# USBBreakout-1_3.net
KiCad netlist of a schematic drawn in EAGLE
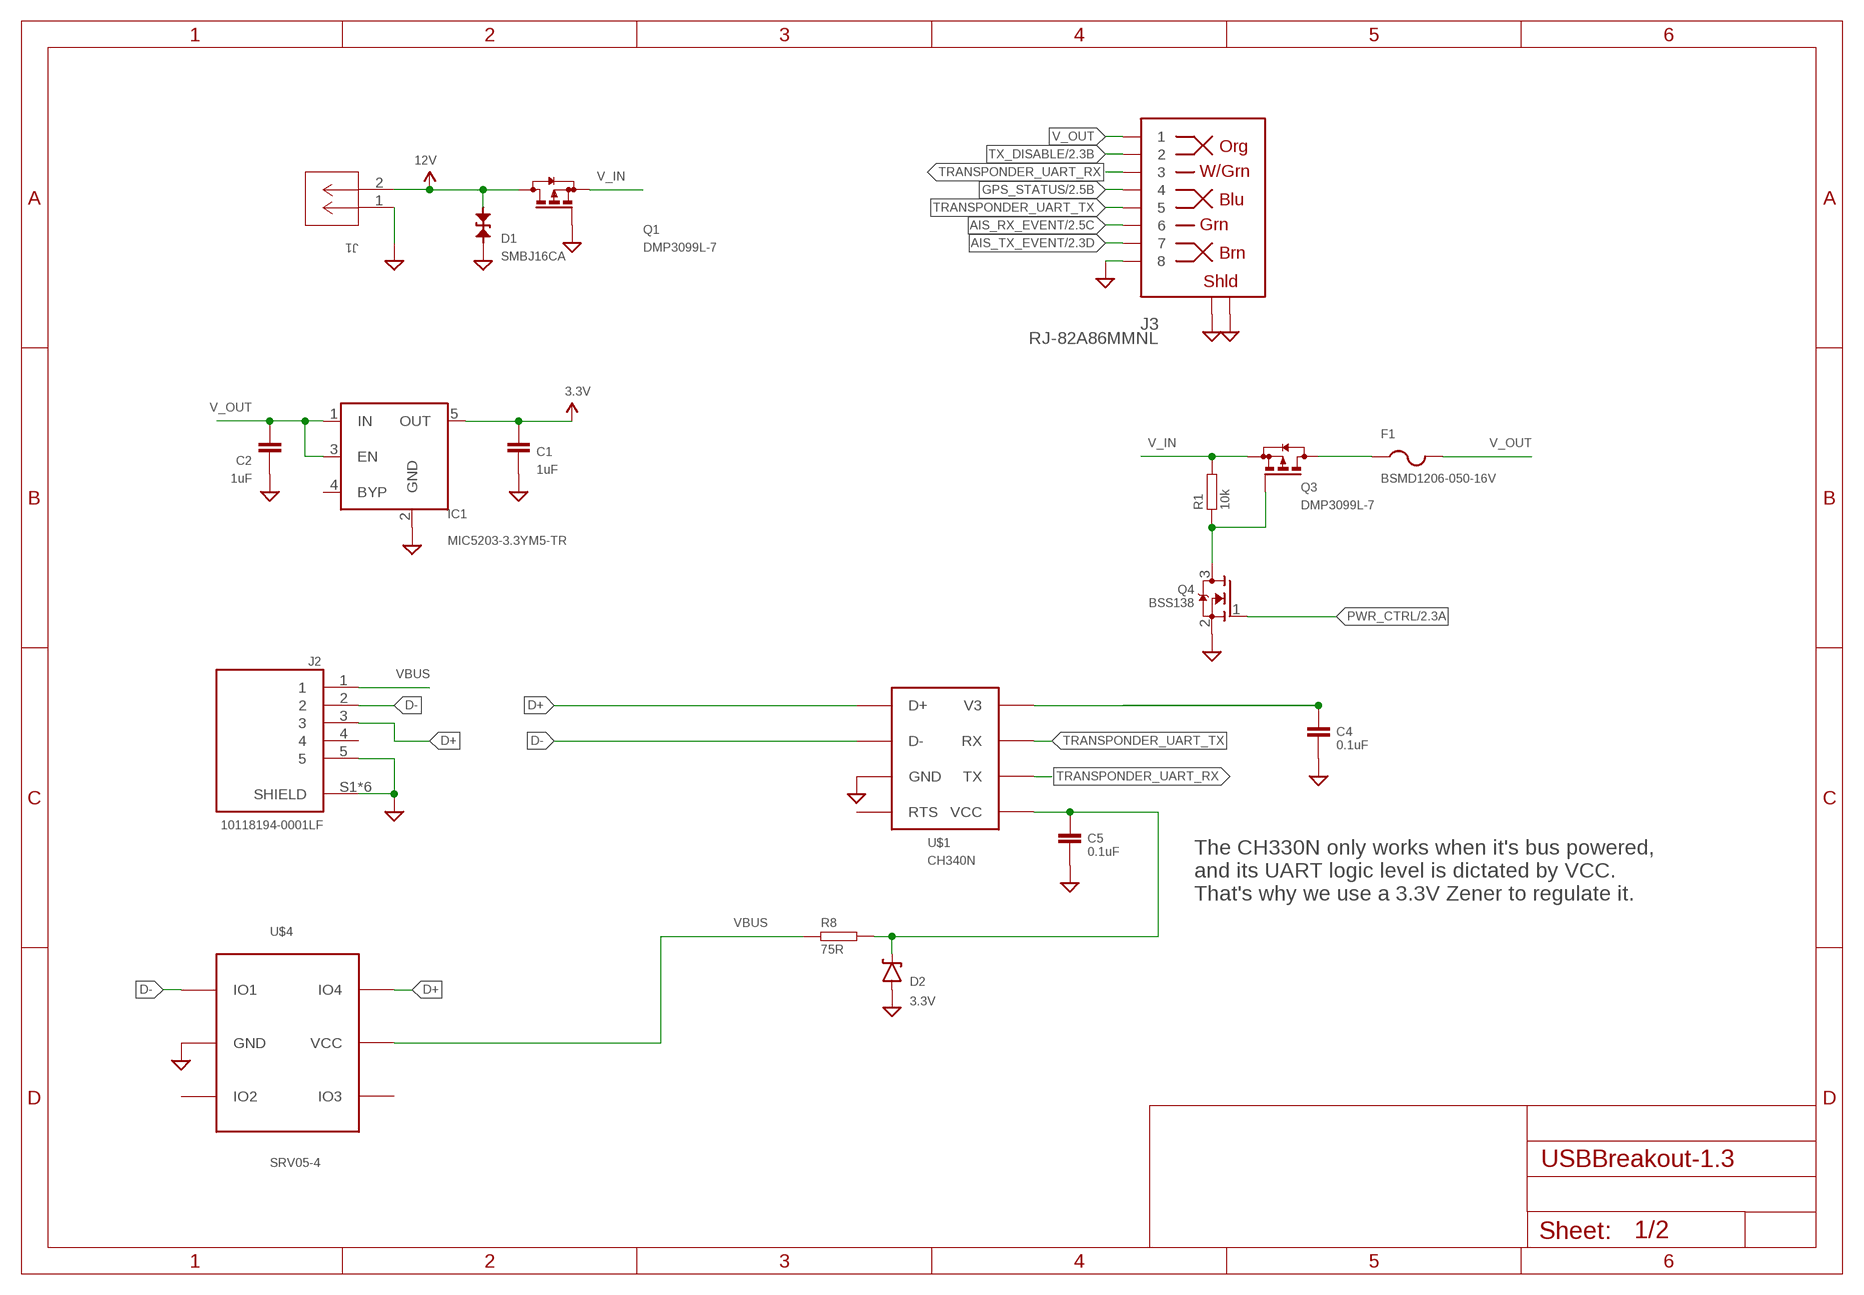
[diagram p0: schematic, sheet 1]
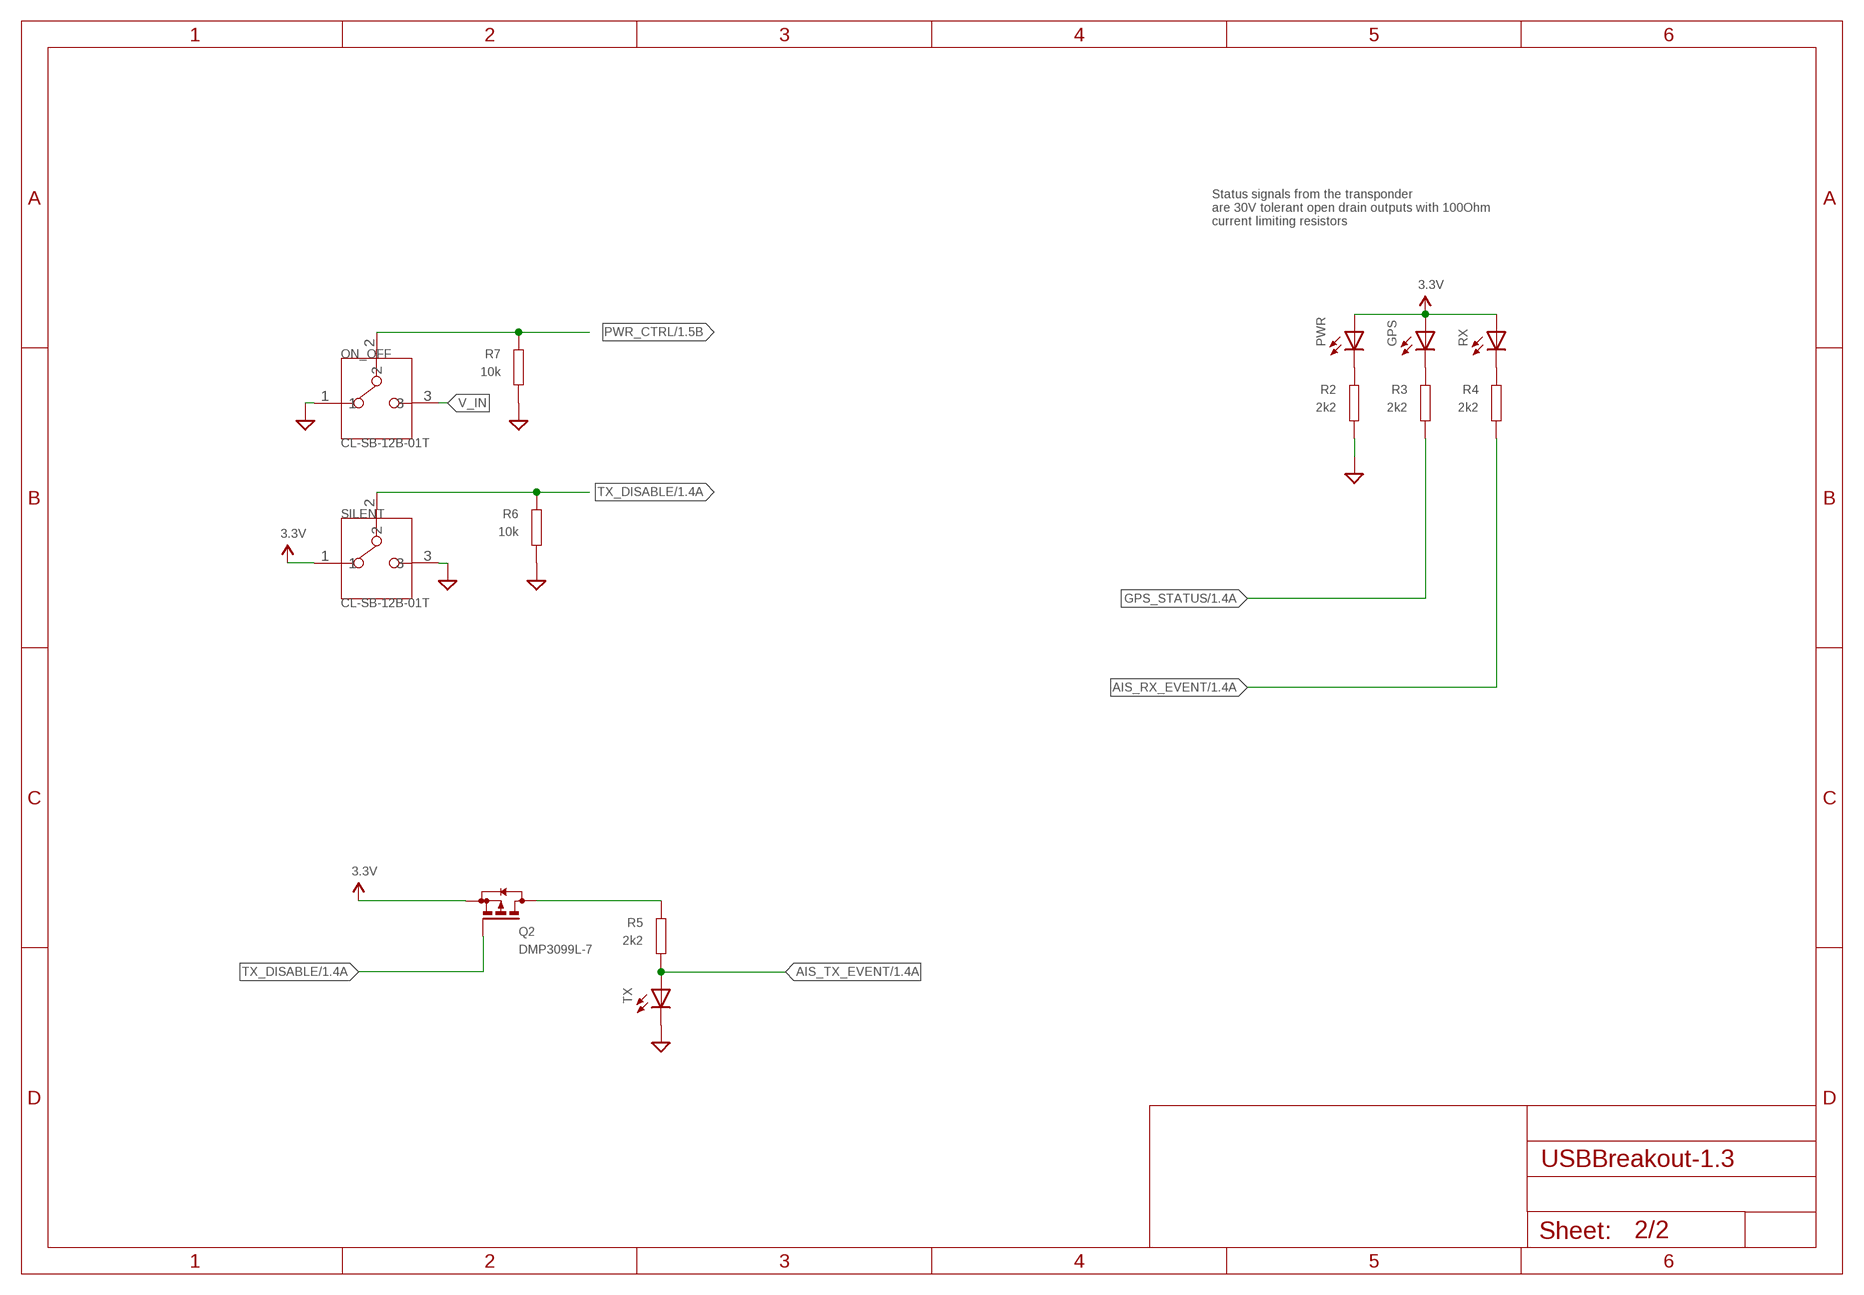
[diagram p1: schematic, sheet 2]

(export (version "E")
  (design (tool "Eeschema 10.0.6"))
  (components
    (comp (ref "GPS")
      (value "LEDCHIPLED_1206")
      (footprint "eagle-import:CHIPLED_1206")
      (fields (field (name "PARTNO") "TJ-S3216CL9T5ALC2G-A5"))
      (libsource (lib "eagle-import") (part "LEDCHIPLED_1206"))
    )
    (comp (ref "ON_OFF")
      (value "CL-SB-12B-01T")
      (footprint "eagle-import:CL-SB-12B")
      (fields (field (name "MF") "Nidec Copal"))
      (libsource (lib "eagle-import") (part "CL-SB-12B-01T"))
    )
    (comp (ref "PWR")
      (value "LEDCHIPLED_1206")
      (footprint "eagle-import:CHIPLED_1206")
      (fields (field (name "PARTNO") "TJ-S3216CL9T5ALC2G-A5"))
      (libsource (lib "eagle-import") (part "LEDCHIPLED_1206"))
    )
    (comp (ref "Q2")
      (value "DMP3099L-7")
      (footprint "eagle-import:SOT23")
      (libsource (lib "eagle-import") (part "BSS84"))
    )
    (comp (ref "R2")
      (value "2k2")
      (footprint "eagle-import:0603")
      (libsource (lib "eagle-import") (part "RESISTOR0603"))
    )
    (comp (ref "R3")
      (value "2k2")
      (footprint "eagle-import:0603")
      (libsource (lib "eagle-import") (part "RESISTOR0603"))
    )
    (comp (ref "R4")
      (value "2k2")
      (footprint "eagle-import:0603")
      (libsource (lib "eagle-import") (part "RESISTOR0603"))
    )
    (comp (ref "R5")
      (value "2k2")
      (footprint "eagle-import:0603")
      (libsource (lib "eagle-import") (part "RESISTOR0603"))
    )
    (comp (ref "R6")
      (value "10k")
      (footprint "eagle-import:0603")
      (libsource (lib "eagle-import") (part "RESISTOR0603"))
    )
    (comp (ref "R7")
      (value "10k")
      (footprint "eagle-import:0603")
      (libsource (lib "eagle-import") (part "RESISTOR0603"))
    )
    (comp (ref "RX")
      (value "LEDCHIPLED_1206")
      (footprint "eagle-import:CHIPLED_1206")
      (fields (field (name "PARTNO") "TJ-S3216CL9T5ALC2G-A5"))
      (libsource (lib "eagle-import") (part "LEDCHIPLED_1206"))
    )
    (comp (ref "SILENT")
      (value "CL-SB-12B-01T")
      (footprint "eagle-import:CL-SB-12B")
      (fields (field (name "MF") "Nidec Copal"))
      (libsource (lib "eagle-import") (part "CL-SB-12B-01T"))
    )
    (comp (ref "TX")
      (value "LEDCHIPLED_1206")
      (footprint "eagle-import:CHIPLED_1206")
      (fields (field (name "PARTNO") "TJ-S3216CL9T5ALC2G-A5"))
      (libsource (lib "eagle-import") (part "LEDCHIPLED_1206"))
    )
    (comp (ref "C1")
      (value "1uF")
      (footprint "eagle-import:0603")
      (libsource (lib "eagle-import") (part "CAPACITOR0603"))
    )
    (comp (ref "C2")
      (value "1uF")
      (footprint "eagle-import:0603")
      (libsource (lib "eagle-import") (part "CAPACITOR0603"))
    )
    (comp (ref "C4")
      (value "0.1uF")
      (footprint "eagle-import:0603")
      (libsource (lib "eagle-import") (part "CAPACITOR0603"))
    )
    (comp (ref "C5")
      (value "0.1uF")
      (footprint "eagle-import:0603")
      (libsource (lib "eagle-import") (part "CAPACITOR0603"))
    )
    (comp (ref "D1")
      (value "SMBJ16CA")
      (footprint "eagle-import:SMB-BIDIR")
      (libsource (lib "eagle-import") (part "DIODE-TVS-BIDIRSMB"))
    )
    (comp (ref "D2")
      (value "3.3V")
      (footprint "eagle-import:SOD-323")
      (libsource (lib "eagle-import") (part "DIODE-ZENER3.3V"))
    )
    (comp (ref "F1")
      (value "BSMD1206-050-16V")
      (footprint "eagle-import:R1206")
      (libsource (lib "eagle-import") (part "PTCFUSE-1206"))
    )
    (comp (ref "IC1")
      (value "MIC5203-3.3YM5-TR")
      (footprint "eagle-import:SOT23-5")
      (libsource (lib "eagle-import") (part "MIC5219XX"))
    )
    (comp (ref "J1")
      (value "OSTVN02A150")
      (footprint "eagle-import:CONN_OSTVN02A150_OST")
      (fields (field (name "COPYRIGHT") "Copyright (C) 2018 Accelerated Designs. All rights reserved"))
      (libsource (lib "eagle-import") (part "OSTVN02A150"))
    )
    (comp (ref "J2")
      (value "10118194-0001LF")
      (footprint "eagle-import:AMPHENOL_10118194-0001LF")
      (fields (field (name "MF") "Amphenol ICC (FCI)"))
      (libsource (lib "eagle-import") (part "10118194-0001LF"))
    )
    (comp (ref "J3")
      (value "RJ-82A86MMNL")
      (footprint "eagle-import:RJ-82A86MMNL")
      (libsource (lib "eagle-import") (part "RJ-82A86MMNL"))
    )
    (comp (ref "Q1")
      (value "DMP3099L-7")
      (footprint "eagle-import:SOT23")
      (libsource (lib "eagle-import") (part "BSS84"))
    )
    (comp (ref "Q3")
      (value "DMP3099L-7")
      (footprint "eagle-import:SOT23")
      (libsource (lib "eagle-import") (part "BSS84"))
    )
    (comp (ref "Q4")
      (value "BSS138")
      (footprint "eagle-import:SOT23")
      (libsource (lib "eagle-import") (part "MOSFET-NREFLOW"))
    )
    (comp (ref "R1")
      (value "10k")
      (footprint "eagle-import:0603")
      (libsource (lib "eagle-import") (part "RESISTOR0603"))
    )
    (comp (ref "R8")
      (value "75R")
      (footprint "eagle-import:0603")
      (libsource (lib "eagle-import") (part "RESISTOR0603"))
    )
    (comp (ref "U$1")
      (value "CH340N")
      (footprint "eagle-import:SOIC-8")
      (libsource (lib "eagle-import") (part "CH330N"))
    )
    (comp (ref "U$4")
      (value "SRV05-4")
      (footprint "eagle-import:SOT23-6")
      (libsource (lib "eagle-import") (part "SRV05-4"))
    )
  )
  (nets
    (net (code "1") (name "3.3V") (class "Default")
      (node (ref "C1") (pin "P$1") (pinfunction "1_P$1") (pintype "passive"))
      (node (ref "GPS") (pin "A") (pinfunction "A_A") (pintype "passive"))
      (node (ref "IC1") (pin "5") (pinfunction "OUT_5") (pintype "output"))
      (node (ref "PWR") (pin "A") (pinfunction "A_A") (pintype "passive"))
      (node (ref "Q2") (pin "2") (pinfunction "S_2") (pintype "passive"))
      (node (ref "RX") (pin "A") (pinfunction "A_A") (pintype "passive"))
      (node (ref "SILENT") (pin "1") (pinfunction "1_1") (pintype "bidirectional"))
    )
    (net (code "2") (name "12V") (class "Default")
      (node (ref "D1") (pin "A") (pinfunction "P$1_A") (pintype "bidirectional"))
      (node (ref "J1") (pin "2") (pinfunction "2_2") (pintype "passive"))
      (node (ref "Q1") (pin "3") (pinfunction "D_3") (pintype "passive"))
    )
    (net (code "3") (name "AIS_RX_EVENT") (class "Default")
      (node (ref "J3") (pin "P$6") (pinfunction "6_P$6") (pintype "bidirectional"))
      (node (ref "R4") (pin "P$2") (pinfunction "P$2_P$2") (pintype "passive"))
    )
    (net (code "4") (name "AIS_TX_EVENT") (class "Default")
      (node (ref "J3") (pin "P$7") (pinfunction "7_P$7") (pintype "bidirectional"))
      (node (ref "R5") (pin "P$2") (pinfunction "P$2_P$2") (pintype "passive"))
      (node (ref "TX") (pin "A") (pinfunction "A_A") (pintype "passive"))
    )
    (net (code "5") (name "D+") (class "Default")
      (node (ref "J2") (pin "3") (pinfunction "3_3") (pintype "passive"))
      (node (ref "U$1") (pin "1") (pinfunction "D+_1") (pintype "bidirectional"))
      (node (ref "U$4") (pin "6") (pinfunction "IO4_6") (pintype "bidirectional"))
    )
    (net (code "6") (name "D-") (class "Default")
      (node (ref "J2") (pin "2") (pinfunction "2_2") (pintype "passive"))
      (node (ref "U$1") (pin "2") (pinfunction "D-_2") (pintype "bidirectional"))
      (node (ref "U$4") (pin "1") (pinfunction "IO1_1") (pintype "bidirectional"))
    )
    (net (code "7") (name "GND") (class "Default")
      (node (ref "C1") (pin "P$2") (pinfunction "2_P$2") (pintype "passive"))
      (node (ref "C2") (pin "P$2") (pinfunction "2_P$2") (pintype "passive"))
      (node (ref "C4") (pin "P$2") (pinfunction "2_P$2") (pintype "passive"))
      (node (ref "C5") (pin "P$2") (pinfunction "2_P$2") (pintype "passive"))
      (node (ref "D1") (pin "C") (pinfunction "P$2_C") (pintype "bidirectional"))
      (node (ref "D2") (pin "A") (pinfunction "A_A") (pintype "passive"))
      (node (ref "IC1") (pin "2") (pinfunction "GND_2") (pintype "power_in"))
      (node (ref "J1") (pin "1") (pinfunction "1_1") (pintype "passive"))
      (node (ref "J2") (pin "5") (pinfunction "5_5") (pintype "passive"))
      (node (ref "J2") (pin "S1") (pinfunction "SHIELD_S1") (pintype "passive"))
      (node (ref "J2") (pin "S2") (pinfunction "SHIELD_S2") (pintype "passive"))
      (node (ref "J2") (pin "S3") (pinfunction "SHIELD_S3") (pintype "passive"))
      (node (ref "J2") (pin "S4") (pinfunction "SHIELD_S4") (pintype "passive"))
      (node (ref "J2") (pin "S5") (pinfunction "SHIELD_S5") (pintype "passive"))
      (node (ref "J2") (pin "S6") (pinfunction "SHIELD_S6") (pintype "passive"))
      (node (ref "J3") (pin "P$10") (pinfunction "SHLD_P$10") (pintype "bidirectional"))
      (node (ref "J3") (pin "P$11") (pinfunction "SHLD_P$11") (pintype "bidirectional"))
      (node (ref "J3") (pin "P$12") (pinfunction "SHLD_P$12") (pintype "bidirectional"))
      (node (ref "J3") (pin "P$8") (pinfunction "8_P$8") (pintype "bidirectional"))
      (node (ref "J3") (pin "P$9") (pinfunction "SHLD_P$9") (pintype "bidirectional"))
      (node (ref "ON_OFF") (pin "1") (pinfunction "1_1") (pintype "bidirectional"))
      (node (ref "Q1") (pin "1") (pinfunction "G_1") (pintype "passive"))
      (node (ref "Q4") (pin "2") (pinfunction "S_2") (pintype "bidirectional"))
      (node (ref "R2") (pin "P$2") (pinfunction "P$2_P$2") (pintype "passive"))
      (node (ref "R6") (pin "P$2") (pinfunction "P$2_P$2") (pintype "passive"))
      (node (ref "R7") (pin "P$2") (pinfunction "P$2_P$2") (pintype "passive"))
      (node (ref "SILENT") (pin "3") (pinfunction "3_3") (pintype "bidirectional"))
      (node (ref "TX") (pin "C") (pinfunction "C_C") (pintype "passive"))
      (node (ref "U$1") (pin "3") (pinfunction "GND_3") (pintype "bidirectional"))
      (node (ref "U$4") (pin "2") (pinfunction "GND_2") (pintype "bidirectional"))
    )
    (net (code "8") (name "GPS_STATUS") (class "Default")
      (node (ref "J3") (pin "P$4") (pinfunction "4_P$4") (pintype "bidirectional"))
      (node (ref "R3") (pin "P$2") (pinfunction "P$2_P$2") (pintype "passive"))
    )
    (net (code "9") (name "Net-(C4-1)") (class "Default")
      (node (ref "C4") (pin "P$1") (pinfunction "1_P$1") (pintype "passive"))
      (node (ref "U$1") (pin "8") (pinfunction "V3_8") (pintype "bidirectional"))
    )
    (net (code "10") (name "Net-(C5-1)") (class "Default")
      (node (ref "C5") (pin "P$1") (pinfunction "1_P$1") (pintype "passive"))
      (node (ref "D2") (pin "C") (pinfunction "C_C") (pintype "passive"))
      (node (ref "R8") (pin "P$2") (pinfunction "P$2_P$2") (pintype "passive"))
      (node (ref "U$1") (pin "5") (pinfunction "VCC_5") (pintype "bidirectional"))
    )
    (net (code "11") (name "Net-(GPS-PadC)") (class "Default")
      (node (ref "GPS") (pin "C") (pinfunction "C_C") (pintype "passive"))
      (node (ref "R3") (pin "P$1") (pinfunction "P$1_P$1") (pintype "passive"))
    )
    (net (code "12") (name "Net-(PWR-PadC)") (class "Default")
      (node (ref "PWR") (pin "C") (pinfunction "C_C") (pintype "passive"))
      (node (ref "R2") (pin "P$1") (pinfunction "P$1_P$1") (pintype "passive"))
    )
    (net (code "13") (name "Net-(Q2-D)") (class "Default")
      (node (ref "Q2") (pin "3") (pinfunction "D_3") (pintype "passive"))
      (node (ref "R5") (pin "P$1") (pinfunction "P$1_P$1") (pintype "passive"))
    )
    (net (code "14") (name "Net-(Q3-D)") (class "Default")
      (node (ref "F1") (pin "1") (pinfunction "1_1") (pintype "passive"))
      (node (ref "Q3") (pin "3") (pinfunction "D_3") (pintype "passive"))
    )
    (net (code "15") (name "Net-(Q3-G)") (class "Default")
      (node (ref "Q3") (pin "1") (pinfunction "G_1") (pintype "passive"))
      (node (ref "Q4") (pin "3") (pinfunction "D_3") (pintype "bidirectional"))
      (node (ref "R1") (pin "P$1") (pinfunction "P$1_P$1") (pintype "passive"))
    )
    (net (code "16") (name "Net-(R4-PadP$1)") (class "Default")
      (node (ref "R4") (pin "P$1") (pinfunction "P$1_P$1") (pintype "passive"))
      (node (ref "RX") (pin "C") (pinfunction "C_C") (pintype "passive"))
    )
    (net (code "17") (name "PWR_CTRL") (class "Default")
      (node (ref "ON_OFF") (pin "2") (pinfunction "2_2") (pintype "bidirectional"))
      (node (ref "Q4") (pin "1") (pinfunction "G_1") (pintype "bidirectional"))
      (node (ref "R7") (pin "P$1") (pinfunction "P$1_P$1") (pintype "passive"))
    )
    (net (code "18") (name "TRANSPONDER_UART_RX") (class "Default")
      (node (ref "J3") (pin "P$3") (pinfunction "3_P$3") (pintype "bidirectional"))
      (node (ref "U$1") (pin "6") (pinfunction "TX_6") (pintype "bidirectional"))
    )
    (net (code "19") (name "TRANSPONDER_UART_TX") (class "Default")
      (node (ref "J3") (pin "P$5") (pinfunction "5_P$5") (pintype "bidirectional"))
      (node (ref "U$1") (pin "7") (pinfunction "RX_7") (pintype "bidirectional"))
    )
    (net (code "20") (name "TX_DISABLE") (class "Default")
      (node (ref "J3") (pin "P$2") (pinfunction "2_P$2") (pintype "bidirectional"))
      (node (ref "Q2") (pin "1") (pinfunction "G_1") (pintype "passive"))
      (node (ref "R6") (pin "P$1") (pinfunction "P$1_P$1") (pintype "passive"))
      (node (ref "SILENT") (pin "2") (pinfunction "2_2") (pintype "bidirectional"))
    )
    (net (code "21") (name "VBUS") (class "Default")
      (node (ref "J2") (pin "1") (pinfunction "1_1") (pintype "passive"))
      (node (ref "R8") (pin "P$1") (pinfunction "P$1_P$1") (pintype "passive"))
      (node (ref "U$4") (pin "5") (pinfunction "VCC_5") (pintype "bidirectional"))
    )
    (net (code "22") (name "V_IN") (class "Default")
      (node (ref "ON_OFF") (pin "3") (pinfunction "3_3") (pintype "bidirectional"))
      (node (ref "Q1") (pin "2") (pinfunction "S_2") (pintype "passive"))
      (node (ref "Q3") (pin "2") (pinfunction "S_2") (pintype "passive"))
      (node (ref "R1") (pin "P$2") (pinfunction "P$2_P$2") (pintype "passive"))
    )
    (net (code "23") (name "V_OUT") (class "Default")
      (node (ref "C2") (pin "P$1") (pinfunction "1_P$1") (pintype "passive"))
      (node (ref "F1") (pin "2") (pinfunction "2_2") (pintype "passive"))
      (node (ref "IC1") (pin "1") (pinfunction "IN_1") (pintype "input"))
      (node (ref "IC1") (pin "3") (pinfunction "EN_3") (pintype "input"))
      (node (ref "J3") (pin "P$1") (pinfunction "1_P$1") (pintype "bidirectional"))
    )
    (net (code "24") (name "unconnected-(IC1-BYP-Pad4)") (class "Default")
      (node (ref "IC1") (pin "4") (pinfunction "BYP_4") (pintype "passive"))
    )
    (net (code "25") (name "unconnected-(J2-Pad4)") (class "Default")
      (node (ref "J2") (pin "4") (pinfunction "4_4") (pintype "passive"))
    )
    (net (code "26") (name "unconnected-(U$1-RTS-Pad4)") (class "Default")
      (node (ref "U$1") (pin "4") (pinfunction "RTS_4") (pintype "bidirectional"))
    )
    (net (code "27") (name "unconnected-(U$4-IO2-Pad3)") (class "Default")
      (node (ref "U$4") (pin "3") (pinfunction "IO2_3") (pintype "bidirectional"))
    )
    (net (code "28") (name "unconnected-(U$4-IO3-Pad4)") (class "Default")
      (node (ref "U$4") (pin "4") (pinfunction "IO3_4") (pintype "bidirectional"))
    )
  )
)
